# driver.net
KiCad netlist of a schematic drawn in EAGLE
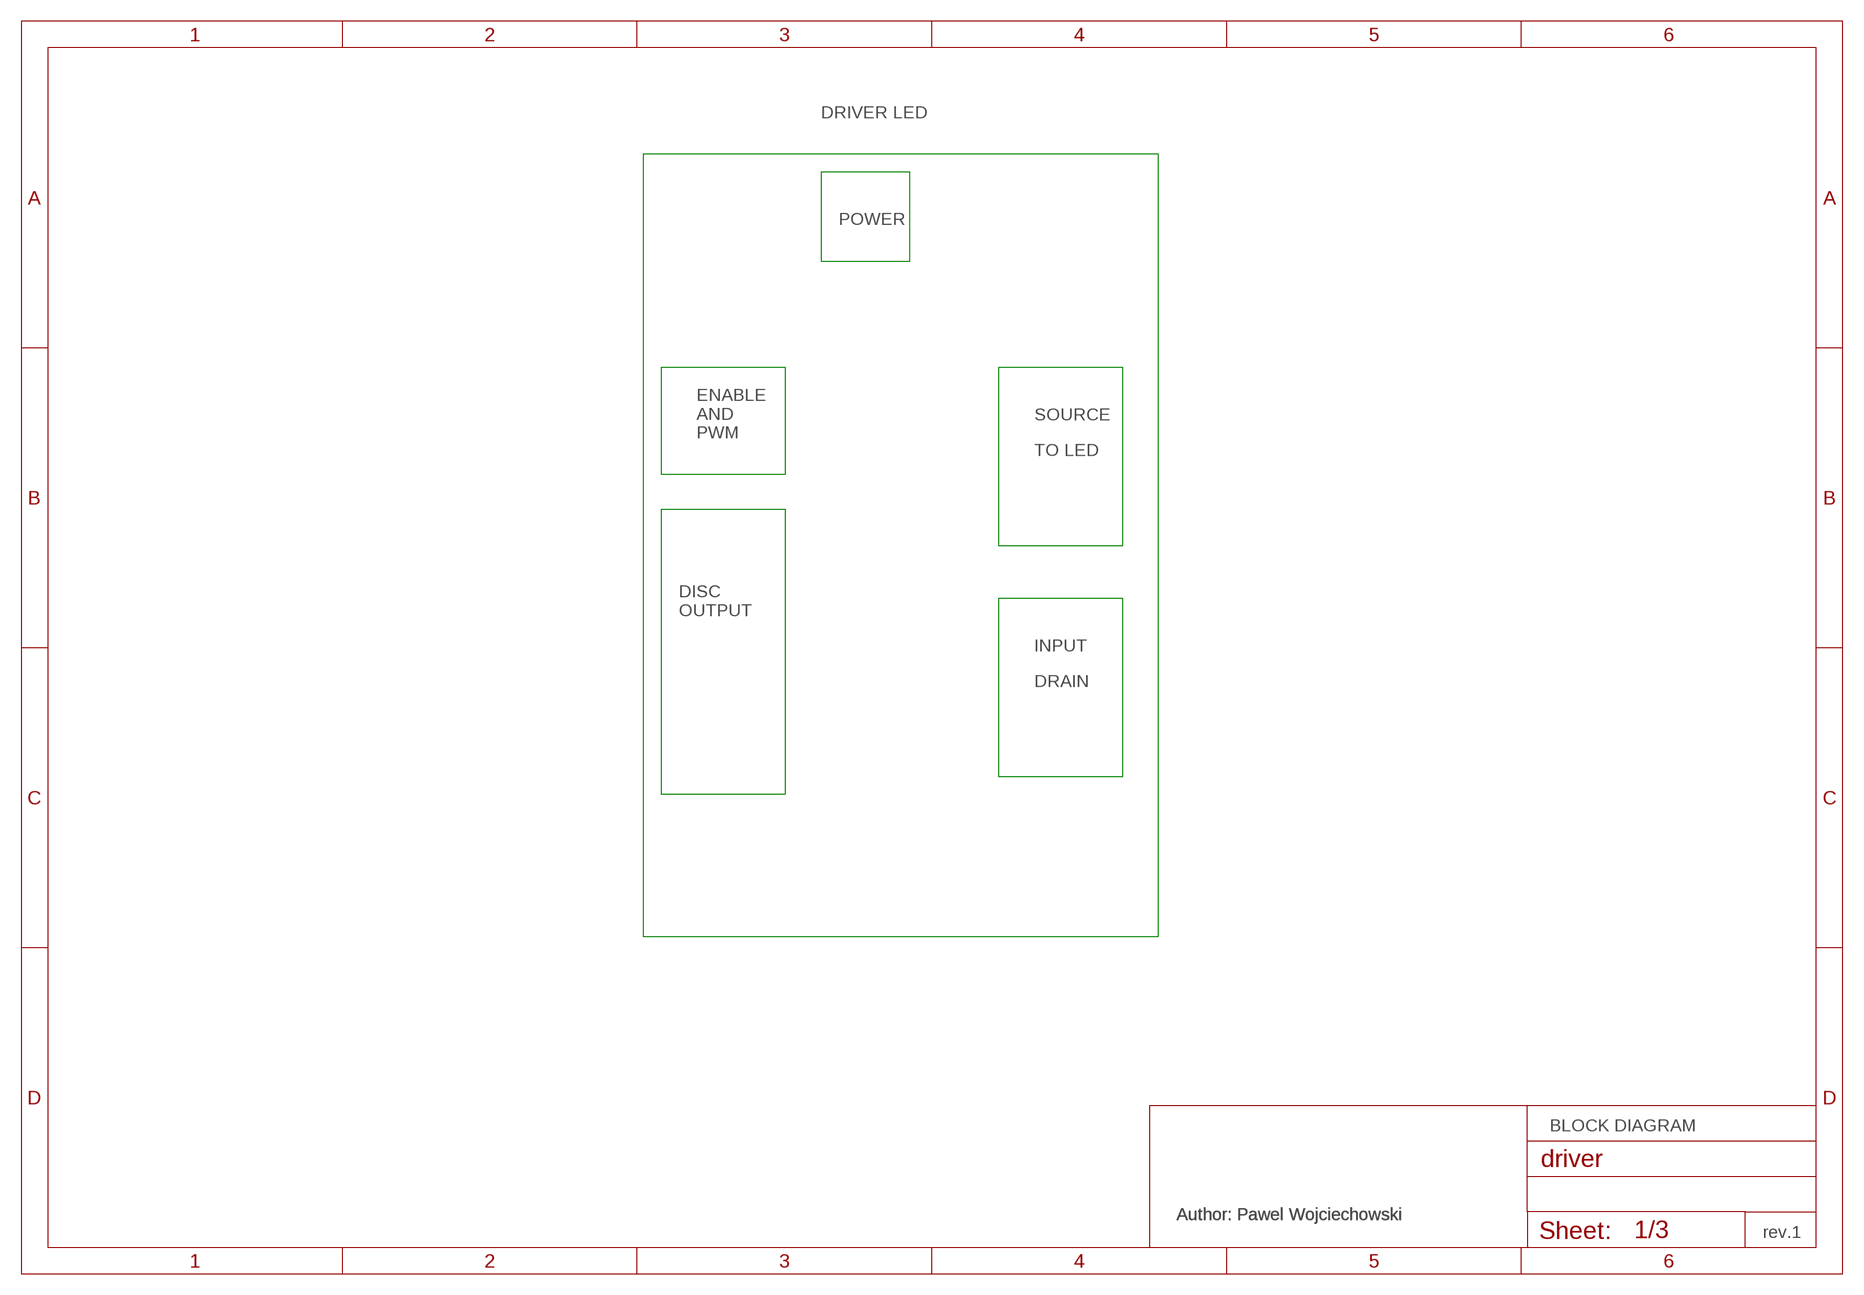
[diagram p0: schematic, sheet 1]
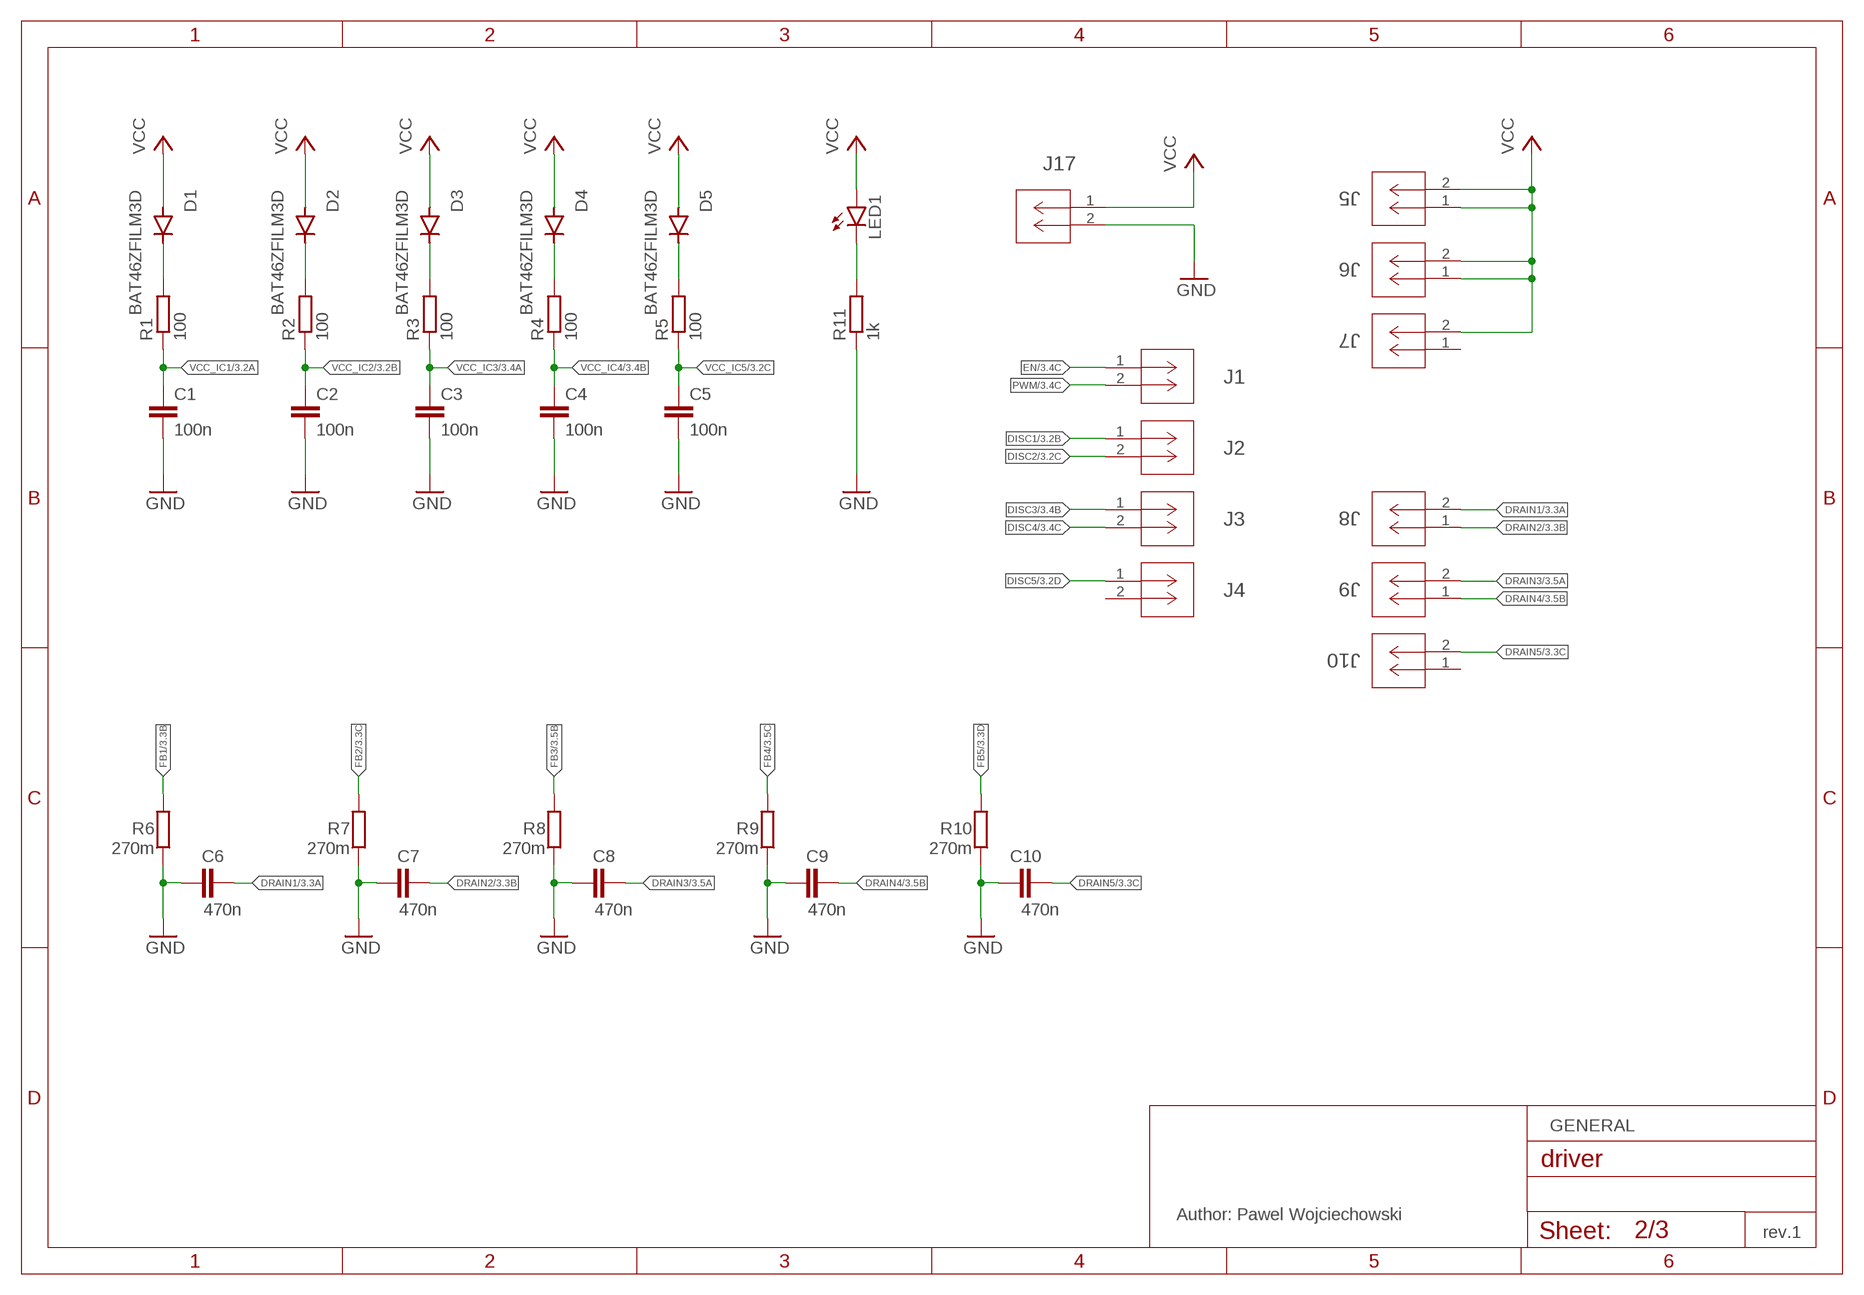
[diagram p1: schematic, sheet 2]
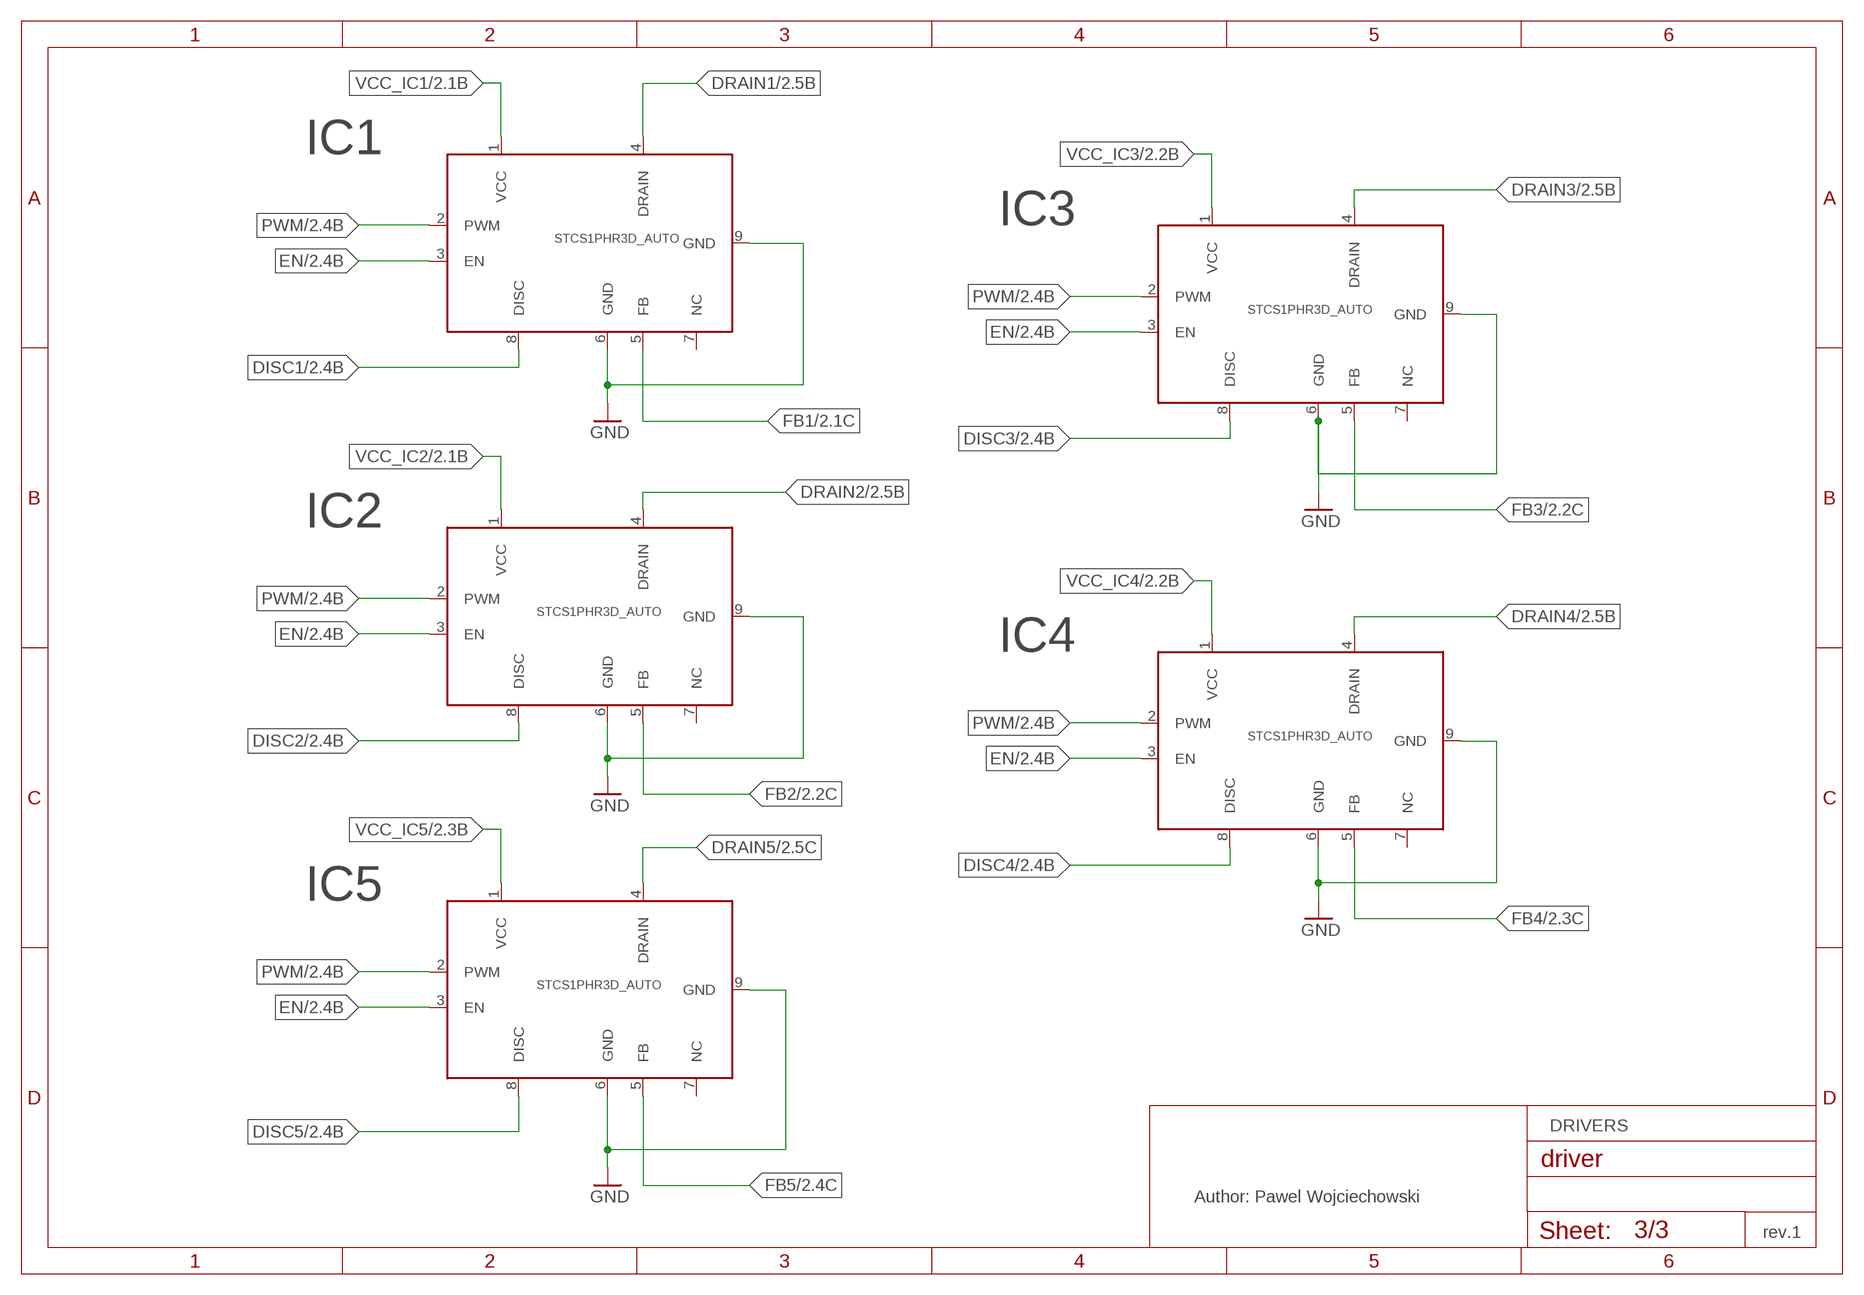
[diagram p2: schematic, sheet 3]

(export (version "E")
  (design (tool "Eeschema 10.0.6"))
  (components
    (comp (ref "IC1")
      (value "STCS1PHR3D_AUTO")
      (footprint "eagle-import:SOIC127P600X170-9T251X320N")
      (libsource (lib "eagle-import") (part "STCS1PHR3D_AUTO"))
    )
    (comp (ref "IC2")
      (value "STCS1PHR3D_AUTO")
      (footprint "eagle-import:SOIC127P600X170-9T251X320N")
      (libsource (lib "eagle-import") (part "STCS1PHR3D_AUTO"))
    )
    (comp (ref "IC3")
      (value "STCS1PHR3D_AUTO")
      (footprint "eagle-import:SOIC127P600X170-9T251X320N")
      (libsource (lib "eagle-import") (part "STCS1PHR3D_AUTO"))
    )
    (comp (ref "IC4")
      (value "STCS1PHR3D_AUTO")
      (footprint "eagle-import:SOIC127P600X170-9T251X320N")
      (libsource (lib "eagle-import") (part "STCS1PHR3D_AUTO"))
    )
    (comp (ref "IC5")
      (value "STCS1PHR3D_AUTO")
      (footprint "eagle-import:SOIC127P600X170-9T251X320N")
      (libsource (lib "eagle-import") (part "STCS1PHR3D_AUTO"))
    )
    (comp (ref "C1")
      (value "100n")
      (footprint "eagle-import:C0603")
      (libsource (lib "eagle-import") (part "C-EUC0603"))
    )
    (comp (ref "C2")
      (value "100n")
      (footprint "eagle-import:C0603")
      (libsource (lib "eagle-import") (part "C-EUC0603"))
    )
    (comp (ref "C3")
      (value "100n")
      (footprint "eagle-import:C0603")
      (libsource (lib "eagle-import") (part "C-EUC0603"))
    )
    (comp (ref "C4")
      (value "100n")
      (footprint "eagle-import:C0603")
      (libsource (lib "eagle-import") (part "C-EUC0603"))
    )
    (comp (ref "C5")
      (value "100n")
      (footprint "eagle-import:C0603")
      (libsource (lib "eagle-import") (part "C-EUC0603"))
    )
    (comp (ref "C6")
      (value "470n")
      (footprint "eagle-import:C0805")
      (libsource (lib "eagle-import") (part "C-EUC0805"))
    )
    (comp (ref "C7")
      (value "470n")
      (footprint "eagle-import:C0805")
      (libsource (lib "eagle-import") (part "C-EUC0805"))
    )
    (comp (ref "C8")
      (value "470n")
      (footprint "eagle-import:C0805")
      (libsource (lib "eagle-import") (part "C-EUC0805"))
    )
    (comp (ref "C9")
      (value "470n")
      (footprint "eagle-import:C0805")
      (libsource (lib "eagle-import") (part "C-EUC0805"))
    )
    (comp (ref "C10")
      (value "470n")
      (footprint "eagle-import:C0805")
      (libsource (lib "eagle-import") (part "C-EUC0805"))
    )
    (comp (ref "D1")
      (value "BAT46ZFILM3D")
      (footprint "eagle-import:SOD-123")
      (libsource (lib "eagle-import") (part "BAT46ZFILM3D"))
    )
    (comp (ref "D2")
      (value "BAT46ZFILM3D")
      (footprint "eagle-import:SOD-123")
      (libsource (lib "eagle-import") (part "BAT46ZFILM3D"))
    )
    (comp (ref "D3")
      (value "BAT46ZFILM3D")
      (footprint "eagle-import:SOD-123")
      (libsource (lib "eagle-import") (part "BAT46ZFILM3D"))
    )
    (comp (ref "D4")
      (value "BAT46ZFILM3D")
      (footprint "eagle-import:SOD-123")
      (libsource (lib "eagle-import") (part "BAT46ZFILM3D"))
    )
    (comp (ref "D5")
      (value "BAT46ZFILM3D")
      (footprint "eagle-import:SOD-123")
      (libsource (lib "eagle-import") (part "BAT46ZFILM3D"))
    )
    (comp (ref "J1")
      (value "1776275-2")
      (footprint "eagle-import:CONN2_1776275-2")
      (fields (field (name "COPYRIGHT") "Copyright (C) 2016 Accelerated Designs. All rights reserved"))
      (libsource (lib "eagle-import") (part "1776275-2"))
    )
    (comp (ref "J2")
      (value "1776275-2")
      (footprint "eagle-import:CONN2_1776275-2")
      (fields (field (name "COPYRIGHT") "Copyright (C) 2016 Accelerated Designs. All rights reserved"))
      (libsource (lib "eagle-import") (part "1776275-2"))
    )
    (comp (ref "J3")
      (value "1776275-2")
      (footprint "eagle-import:CONN2_1776275-2")
      (fields (field (name "COPYRIGHT") "Copyright (C) 2016 Accelerated Designs. All rights reserved"))
      (libsource (lib "eagle-import") (part "1776275-2"))
    )
    (comp (ref "J4")
      (value "1776275-2")
      (footprint "eagle-import:CONN2_1776275-2")
      (fields (field (name "COPYRIGHT") "Copyright (C) 2016 Accelerated Designs. All rights reserved"))
      (libsource (lib "eagle-import") (part "1776275-2"))
    )
    (comp (ref "J5")
      (value "1776275-2")
      (footprint "eagle-import:CONN2_1776275-2")
      (fields (field (name "COPYRIGHT") "Copyright (C) 2016 Accelerated Designs. All rights reserved"))
      (libsource (lib "eagle-import") (part "1776275-2"))
    )
    (comp (ref "J6")
      (value "1776275-2")
      (footprint "eagle-import:CONN2_1776275-2")
      (fields (field (name "COPYRIGHT") "Copyright (C) 2016 Accelerated Designs. All rights reserved"))
      (libsource (lib "eagle-import") (part "1776275-2"))
    )
    (comp (ref "J7")
      (value "1776275-2")
      (footprint "eagle-import:CONN2_1776275-2")
      (fields (field (name "COPYRIGHT") "Copyright (C) 2016 Accelerated Designs. All rights reserved"))
      (libsource (lib "eagle-import") (part "1776275-2"))
    )
    (comp (ref "J8")
      (value "1776275-2")
      (footprint "eagle-import:CONN2_1776275-2")
      (fields (field (name "COPYRIGHT") "Copyright (C) 2016 Accelerated Designs. All rights reserved"))
      (libsource (lib "eagle-import") (part "1776275-2"))
    )
    (comp (ref "J9")
      (value "1776275-2")
      (footprint "eagle-import:CONN2_1776275-2")
      (fields (field (name "COPYRIGHT") "Copyright (C) 2016 Accelerated Designs. All rights reserved"))
      (libsource (lib "eagle-import") (part "1776275-2"))
    )
    (comp (ref "J10")
      (value "1776275-2")
      (footprint "eagle-import:CONN2_1776275-2")
      (fields (field (name "COPYRIGHT") "Copyright (C) 2016 Accelerated Designs. All rights reserved"))
      (libsource (lib "eagle-import") (part "1776275-2"))
    )
    (comp (ref "J17")
      (value "1776275-2")
      (footprint "eagle-import:CONN2_1776275-2")
      (fields (field (name "COPYRIGHT") "Copyright (C) 2016 Accelerated Designs. All rights reserved"))
      (libsource (lib "eagle-import") (part "1776275-2"))
    )
    (comp (ref "LED1")
      (value "LEDSMT1206")
      (footprint "eagle-import:1206")
      (libsource (lib "eagle-import") (part "LEDSMT1206"))
    )
    (comp (ref "R1")
      (value "100")
      (footprint "eagle-import:R0603")
      (libsource (lib "eagle-import") (part "R-EU_R0603"))
    )
    (comp (ref "R2")
      (value "100")
      (footprint "eagle-import:R0603")
      (libsource (lib "eagle-import") (part "R-EU_R0603"))
    )
    (comp (ref "R3")
      (value "100")
      (footprint "eagle-import:R0603")
      (libsource (lib "eagle-import") (part "R-EU_R0603"))
    )
    (comp (ref "R4")
      (value "100")
      (footprint "eagle-import:R0603")
      (libsource (lib "eagle-import") (part "R-EU_R0603"))
    )
    (comp (ref "R5")
      (value "100")
      (footprint "eagle-import:R0603")
      (libsource (lib "eagle-import") (part "R-EU_R0603"))
    )
    (comp (ref "R6")
      (value "270m")
      (footprint "eagle-import:R0603")
      (libsource (lib "eagle-import") (part "R-EU_R0603"))
    )
    (comp (ref "R7")
      (value "270m")
      (footprint "eagle-import:R0603")
      (libsource (lib "eagle-import") (part "R-EU_R0603"))
    )
    (comp (ref "R8")
      (value "270m")
      (footprint "eagle-import:R0603")
      (libsource (lib "eagle-import") (part "R-EU_R0603"))
    )
    (comp (ref "R9")
      (value "270m")
      (footprint "eagle-import:R0603")
      (libsource (lib "eagle-import") (part "R-EU_R0603"))
    )
    (comp (ref "R10")
      (value "270m")
      (footprint "eagle-import:R0603")
      (libsource (lib "eagle-import") (part "R-EU_R0603"))
    )
    (comp (ref "R11")
      (value "1k")
      (footprint "eagle-import:R0603")
      (libsource (lib "eagle-import") (part "R-EU_R0603"))
    )
  )
  (nets
    (net (code "1") (name "DISC1") (class "Default")
      (node (ref "IC1") (pin "8") (pinfunction "DISC_8") (pintype "output"))
      (node (ref "J2") (pin "1") (pinfunction "1_1") (pintype "passive"))
    )
    (net (code "2") (name "DISC2") (class "Default")
      (node (ref "IC2") (pin "8") (pinfunction "DISC_8") (pintype "output"))
      (node (ref "J2") (pin "2") (pinfunction "2_2") (pintype "passive"))
    )
    (net (code "3") (name "DISC3") (class "Default")
      (node (ref "IC3") (pin "8") (pinfunction "DISC_8") (pintype "output"))
      (node (ref "J3") (pin "1") (pinfunction "1_1") (pintype "passive"))
    )
    (net (code "4") (name "DISC4") (class "Default")
      (node (ref "IC4") (pin "8") (pinfunction "DISC_8") (pintype "output"))
      (node (ref "J3") (pin "2") (pinfunction "2_2") (pintype "passive"))
    )
    (net (code "5") (name "DISC5") (class "Default")
      (node (ref "IC5") (pin "8") (pinfunction "DISC_8") (pintype "output"))
      (node (ref "J4") (pin "1") (pinfunction "1_1") (pintype "passive"))
    )
    (net (code "6") (name "DRAIN1") (class "Default")
      (node (ref "C6") (pin "2") (pinfunction "2_2") (pintype "passive"))
      (node (ref "IC1") (pin "4") (pinfunction "DRAIN_4") (pintype "bidirectional"))
      (node (ref "J8") (pin "2") (pinfunction "2_2") (pintype "passive"))
    )
    (net (code "7") (name "DRAIN2") (class "Default")
      (node (ref "C7") (pin "2") (pinfunction "2_2") (pintype "passive"))
      (node (ref "IC2") (pin "4") (pinfunction "DRAIN_4") (pintype "bidirectional"))
      (node (ref "J8") (pin "1") (pinfunction "1_1") (pintype "passive"))
    )
    (net (code "8") (name "DRAIN3") (class "Default")
      (node (ref "C8") (pin "2") (pinfunction "2_2") (pintype "passive"))
      (node (ref "IC3") (pin "4") (pinfunction "DRAIN_4") (pintype "bidirectional"))
      (node (ref "J9") (pin "2") (pinfunction "2_2") (pintype "passive"))
    )
    (net (code "9") (name "DRAIN4") (class "Default")
      (node (ref "C9") (pin "2") (pinfunction "2_2") (pintype "passive"))
      (node (ref "IC4") (pin "4") (pinfunction "DRAIN_4") (pintype "bidirectional"))
      (node (ref "J9") (pin "1") (pinfunction "1_1") (pintype "passive"))
    )
    (net (code "10") (name "DRAIN5") (class "Default")
      (node (ref "C10") (pin "2") (pinfunction "2_2") (pintype "passive"))
      (node (ref "IC5") (pin "4") (pinfunction "DRAIN_4") (pintype "bidirectional"))
      (node (ref "J10") (pin "2") (pinfunction "2_2") (pintype "passive"))
    )
    (net (code "11") (name "EN") (class "Default")
      (node (ref "IC1") (pin "3") (pinfunction "EN_3") (pintype "input"))
      (node (ref "IC2") (pin "3") (pinfunction "EN_3") (pintype "input"))
      (node (ref "IC3") (pin "3") (pinfunction "EN_3") (pintype "input"))
      (node (ref "IC4") (pin "3") (pinfunction "EN_3") (pintype "input"))
      (node (ref "IC5") (pin "3") (pinfunction "EN_3") (pintype "input"))
      (node (ref "J1") (pin "1") (pinfunction "1_1") (pintype "passive"))
    )
    (net (code "12") (name "FB1") (class "Default")
      (node (ref "IC1") (pin "5") (pinfunction "FB_5") (pintype "bidirectional"))
      (node (ref "R6") (pin "2") (pinfunction "2_2") (pintype "passive"))
    )
    (net (code "13") (name "FB2") (class "Default")
      (node (ref "IC2") (pin "5") (pinfunction "FB_5") (pintype "bidirectional"))
      (node (ref "R7") (pin "2") (pinfunction "2_2") (pintype "passive"))
    )
    (net (code "14") (name "FB3") (class "Default")
      (node (ref "IC3") (pin "5") (pinfunction "FB_5") (pintype "bidirectional"))
      (node (ref "R8") (pin "2") (pinfunction "2_2") (pintype "passive"))
    )
    (net (code "15") (name "FB4") (class "Default")
      (node (ref "IC4") (pin "5") (pinfunction "FB_5") (pintype "bidirectional"))
      (node (ref "R9") (pin "2") (pinfunction "2_2") (pintype "passive"))
    )
    (net (code "16") (name "FB5") (class "Default")
      (node (ref "IC5") (pin "5") (pinfunction "FB_5") (pintype "bidirectional"))
      (node (ref "R10") (pin "2") (pinfunction "2_2") (pintype "passive"))
    )
    (net (code "17") (name "GND") (class "Default")
      (node (ref "C1") (pin "2") (pinfunction "2_2") (pintype "passive"))
      (node (ref "C10") (pin "1") (pinfunction "1_1") (pintype "passive"))
      (node (ref "C2") (pin "2") (pinfunction "2_2") (pintype "passive"))
      (node (ref "C3") (pin "2") (pinfunction "2_2") (pintype "passive"))
      (node (ref "C4") (pin "2") (pinfunction "2_2") (pintype "passive"))
      (node (ref "C5") (pin "2") (pinfunction "2_2") (pintype "passive"))
      (node (ref "C6") (pin "1") (pinfunction "1_1") (pintype "passive"))
      (node (ref "C7") (pin "1") (pinfunction "1_1") (pintype "passive"))
      (node (ref "C8") (pin "1") (pinfunction "1_1") (pintype "passive"))
      (node (ref "C9") (pin "1") (pinfunction "1_1") (pintype "passive"))
      (node (ref "IC1") (pin "6") (pinfunction "GND_6") (pintype "bidirectional"))
      (node (ref "IC1") (pin "9") (pinfunction "GND_9") (pintype "bidirectional"))
      (node (ref "IC2") (pin "6") (pinfunction "GND_6") (pintype "bidirectional"))
      (node (ref "IC2") (pin "9") (pinfunction "GND_9") (pintype "bidirectional"))
      (node (ref "IC3") (pin "6") (pinfunction "GND_6") (pintype "bidirectional"))
      (node (ref "IC3") (pin "9") (pinfunction "GND_9") (pintype "bidirectional"))
      (node (ref "IC4") (pin "6") (pinfunction "GND_6") (pintype "bidirectional"))
      (node (ref "IC4") (pin "9") (pinfunction "GND_9") (pintype "bidirectional"))
      (node (ref "IC5") (pin "6") (pinfunction "GND_6") (pintype "bidirectional"))
      (node (ref "IC5") (pin "9") (pinfunction "GND_9") (pintype "bidirectional"))
      (node (ref "J17") (pin "2") (pinfunction "2_2") (pintype "passive"))
      (node (ref "R10") (pin "1") (pinfunction "1_1") (pintype "passive"))
      (node (ref "R11") (pin "1") (pinfunction "1_1") (pintype "passive"))
      (node (ref "R6") (pin "1") (pinfunction "1_1") (pintype "passive"))
      (node (ref "R7") (pin "1") (pinfunction "1_1") (pintype "passive"))
      (node (ref "R8") (pin "1") (pinfunction "1_1") (pintype "passive"))
      (node (ref "R9") (pin "1") (pinfunction "1_1") (pintype "passive"))
    )
    (net (code "18") (name "Net-(D1-PadC)") (class "Default")
      (node (ref "D1") (pin "C") (pinfunction "C_C") (pintype "passive"))
      (node (ref "R1") (pin "2") (pinfunction "2_2") (pintype "passive"))
    )
    (net (code "19") (name "Net-(D2-PadC)") (class "Default")
      (node (ref "D2") (pin "C") (pinfunction "C_C") (pintype "passive"))
      (node (ref "R2") (pin "2") (pinfunction "2_2") (pintype "passive"))
    )
    (net (code "20") (name "Net-(D3-PadC)") (class "Default")
      (node (ref "D3") (pin "C") (pinfunction "C_C") (pintype "passive"))
      (node (ref "R3") (pin "2") (pinfunction "2_2") (pintype "passive"))
    )
    (net (code "21") (name "Net-(D4-PadC)") (class "Default")
      (node (ref "D4") (pin "C") (pinfunction "C_C") (pintype "passive"))
      (node (ref "R4") (pin "2") (pinfunction "2_2") (pintype "passive"))
    )
    (net (code "22") (name "Net-(D5-PadC)") (class "Default")
      (node (ref "D5") (pin "C") (pinfunction "C_C") (pintype "passive"))
      (node (ref "R5") (pin "2") (pinfunction "2_2") (pintype "passive"))
    )
    (net (code "23") (name "Net-(LED1-PadC)") (class "Default")
      (node (ref "LED1") (pin "C") (pinfunction "C_C") (pintype "passive"))
      (node (ref "R11") (pin "2") (pinfunction "2_2") (pintype "passive"))
    )
    (net (code "24") (name "PWM") (class "Default")
      (node (ref "IC1") (pin "2") (pinfunction "PWM_2") (pintype "input"))
      (node (ref "IC2") (pin "2") (pinfunction "PWM_2") (pintype "input"))
      (node (ref "IC3") (pin "2") (pinfunction "PWM_2") (pintype "input"))
      (node (ref "IC4") (pin "2") (pinfunction "PWM_2") (pintype "input"))
      (node (ref "IC5") (pin "2") (pinfunction "PWM_2") (pintype "input"))
      (node (ref "J1") (pin "2") (pinfunction "2_2") (pintype "passive"))
    )
    (net (code "25") (name "VCC") (class "Default")
      (node (ref "D1") (pin "A") (pinfunction "A_A") (pintype "passive"))
      (node (ref "D2") (pin "A") (pinfunction "A_A") (pintype "passive"))
      (node (ref "D3") (pin "A") (pinfunction "A_A") (pintype "passive"))
      (node (ref "D4") (pin "A") (pinfunction "A_A") (pintype "passive"))
      (node (ref "D5") (pin "A") (pinfunction "A_A") (pintype "passive"))
      (node (ref "J17") (pin "1") (pinfunction "1_1") (pintype "passive"))
      (node (ref "J5") (pin "1") (pinfunction "1_1") (pintype "passive"))
      (node (ref "J5") (pin "2") (pinfunction "2_2") (pintype "passive"))
      (node (ref "J6") (pin "1") (pinfunction "1_1") (pintype "passive"))
      (node (ref "J6") (pin "2") (pinfunction "2_2") (pintype "passive"))
      (node (ref "J7") (pin "2") (pinfunction "2_2") (pintype "passive"))
      (node (ref "LED1") (pin "A") (pinfunction "A_A") (pintype "passive"))
    )
    (net (code "26") (name "VCC_IC1") (class "Default")
      (node (ref "C1") (pin "1") (pinfunction "1_1") (pintype "passive"))
      (node (ref "IC1") (pin "1") (pinfunction "VCC_1") (pintype "bidirectional"))
      (node (ref "R1") (pin "1") (pinfunction "1_1") (pintype "passive"))
    )
    (net (code "27") (name "VCC_IC2") (class "Default")
      (node (ref "C2") (pin "1") (pinfunction "1_1") (pintype "passive"))
      (node (ref "IC2") (pin "1") (pinfunction "VCC_1") (pintype "bidirectional"))
      (node (ref "R2") (pin "1") (pinfunction "1_1") (pintype "passive"))
    )
    (net (code "28") (name "VCC_IC3") (class "Default")
      (node (ref "C3") (pin "1") (pinfunction "1_1") (pintype "passive"))
      (node (ref "IC3") (pin "1") (pinfunction "VCC_1") (pintype "bidirectional"))
      (node (ref "R3") (pin "1") (pinfunction "1_1") (pintype "passive"))
    )
    (net (code "29") (name "VCC_IC4") (class "Default")
      (node (ref "C4") (pin "1") (pinfunction "1_1") (pintype "passive"))
      (node (ref "IC4") (pin "1") (pinfunction "VCC_1") (pintype "bidirectional"))
      (node (ref "R4") (pin "1") (pinfunction "1_1") (pintype "passive"))
    )
    (net (code "30") (name "VCC_IC5") (class "Default")
      (node (ref "C5") (pin "1") (pinfunction "1_1") (pintype "passive"))
      (node (ref "IC5") (pin "1") (pinfunction "VCC_1") (pintype "bidirectional"))
      (node (ref "R5") (pin "1") (pinfunction "1_1") (pintype "passive"))
    )
    (net (code "31") (name "unconnected-(IC1-NC-Pad7)") (class "Default")
      (node (ref "IC1") (pin "7") (pinfunction "NC_7") (pintype "bidirectional"))
    )
    (net (code "32") (name "unconnected-(IC2-NC-Pad7)") (class "Default")
      (node (ref "IC2") (pin "7") (pinfunction "NC_7") (pintype "bidirectional"))
    )
    (net (code "33") (name "unconnected-(IC3-NC-Pad7)") (class "Default")
      (node (ref "IC3") (pin "7") (pinfunction "NC_7") (pintype "bidirectional"))
    )
    (net (code "34") (name "unconnected-(IC4-NC-Pad7)") (class "Default")
      (node (ref "IC4") (pin "7") (pinfunction "NC_7") (pintype "bidirectional"))
    )
    (net (code "35") (name "unconnected-(IC5-NC-Pad7)") (class "Default")
      (node (ref "IC5") (pin "7") (pinfunction "NC_7") (pintype "bidirectional"))
    )
    (net (code "36") (name "unconnected-(J4-Pad2)") (class "Default")
      (node (ref "J4") (pin "2") (pinfunction "2_2") (pintype "passive"))
    )
    (net (code "37") (name "unconnected-(J7-Pad1)") (class "Default")
      (node (ref "J7") (pin "1") (pinfunction "1_1") (pintype "passive"))
    )
    (net (code "38") (name "unconnected-(J10-Pad1)") (class "Default")
      (node (ref "J10") (pin "1") (pinfunction "1_1") (pintype "passive"))
    )
  )
)
